# SensorCaida.net
KiCad netlist of a schematic drawn in Altium Designer
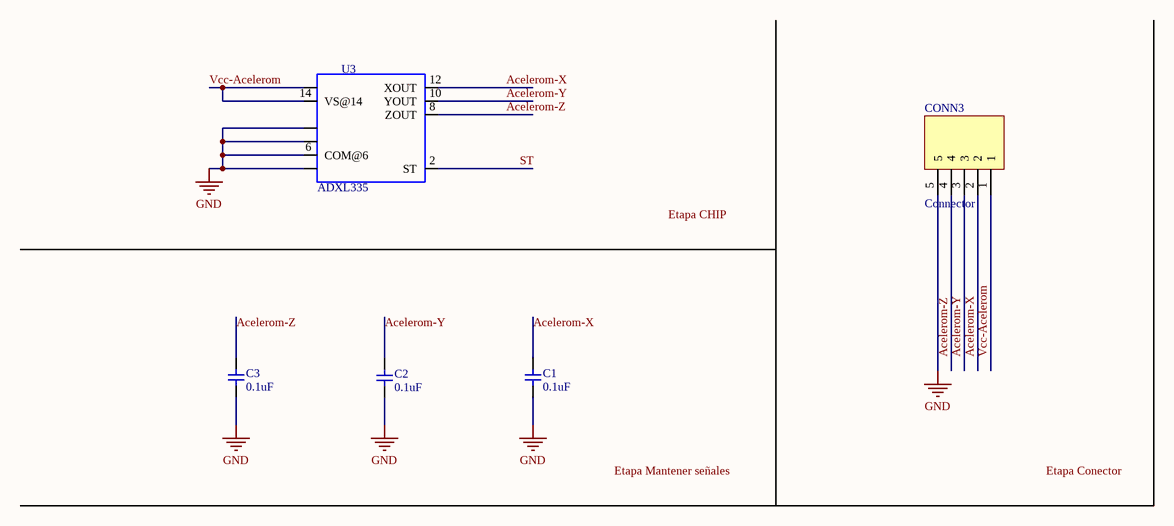
[diagram p0: SensorCaida.SchDoc]

(export (version "E")
  (design (tool "Eeschema 10.0.6"))
  (components
    (comp (ref "C1")
      (value "0.1uF")
      (footprint "C1206-1.00")
      (description "Capacitor, generic")
      (fields (field (name "Comment") "C"))
      (libsource (lib "IFS_Altium") (part "C"))
    )
    (comp (ref "C2")
      (value "0.1uF")
      (footprint "C1206-1.00")
      (description "Capacitor, generic")
      (fields (field (name "Comment") "C"))
      (libsource (lib "IFS_Altium") (part "C"))
    )
    (comp (ref "C3")
      (value "0.1uF")
      (footprint "C1206-1.00")
      (description "Capacitor, generic")
      (fields (field (name "Comment") "C"))
      (libsource (lib "IFS_Altium") (part "C"))
    )
    (comp (ref "CONN3")
      (value "Connector")
      (footprint "1x5x2.54 Pin Header TH V")
      (libsource (lib "IFS_Altium") (part "Header 1x5"))
    )
    (comp (ref "U3")
      (value "ADXL335")
      (footprint "*LFCSP-16")
      (description "AcelerÃ³metro X, Y, Eje Z Â± 3g 1.6kHz _X, Y_, 550Hz _Z_ 16-LFCSP-LQ _4x4_")
      (fields (field (name "MF") "Analog Devices"))
      (libsource (lib "ADXL335") (part "ADXL335"))
    )
  )
  (nets
    (net (code "1") (name "/Acelerom-X") (class "Default")
      (node (ref "C1") (pin "1") (pinfunction "1_1") (pintype "passive"))
      (node (ref "CONN3") (pin "2") (pinfunction "2_2") (pintype "passive"))
      (node (ref "U3") (pin "12") (pinfunction "XOUT_12") (pintype "bidirectional"))
    )
    (net (code "2") (name "/Acelerom-Y") (class "Default")
      (node (ref "CONN3") (pin "3") (pinfunction "3_3") (pintype "passive"))
      (node (ref "U3") (pin "10") (pinfunction "YOUT_10") (pintype "bidirectional"))
    )
    (net (code "3") (name "/Acelerom-Z") (class "Default")
      (node (ref "C3") (pin "1") (pinfunction "1_1") (pintype "passive"))
      (node (ref "CONN3") (pin "4") (pinfunction "4_4") (pintype "passive"))
      (node (ref "U3") (pin "8") (pinfunction "ZOUT_8") (pintype "bidirectional"))
    )
    (net (code "7") (name "/ST") (class "Default")
      (node (ref "U3") (pin "2") (pinfunction "ST_2") (pintype "bidirectional"))
    )
    (net (code "8") (name "/Vcc-Acelerom") (class "Default")
      (node (ref "CONN3") (pin "1") (pinfunction "1_1") (pintype "passive"))
      (node (ref "U3") (pin "14") (pinfunction "VS@14_14") (pintype "bidirectional"))
      (node (ref "U3") (pin "15") (pinfunction "VS@15_15") (pintype "bidirectional"))
    )
    (net (code "9") (name "GND") (class "Default")
      (node (ref "C2") (pin "2") (pinfunction "2_2") (pintype "passive"))
      (node (ref "C3") (pin "2") (pinfunction "2_2") (pintype "passive"))
      (node (ref "CONN3") (pin "5") (pinfunction "5_5") (pintype "passive"))
      (node (ref "U3") (pin "3") (pinfunction "COM@3_3") (pintype "bidirectional"))
      (node (ref "U3") (pin "5") (pinfunction "COM@5_5") (pintype "bidirectional"))
      (node (ref "U3") (pin "6") (pinfunction "COM@6_6") (pintype "bidirectional"))
      (node (ref "U3") (pin "7") (pinfunction "COM@7_7") (pintype "bidirectional"))
    )
    (net (code "10") (name "unconnected-(C1-Pad2)") (class "Default")
      (node (ref "C1") (pin "2") (pinfunction "2_2") (pintype "passive"))
    )
    (net (code "11") (name "unconnected-(C2-Pad1)") (class "Default")
      (node (ref "C2") (pin "1") (pinfunction "1_1") (pintype "passive"))
    )
  )
)
